# BME280.net
KiCad netlist of a schematic drawn in Altium Designer
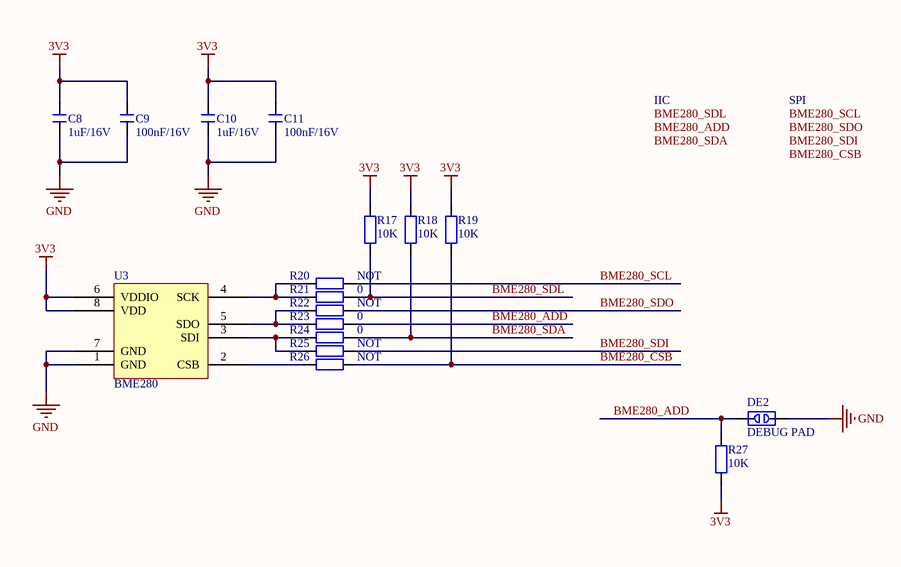
[diagram p0: BME280.SchDoc]

(export (version "E")
  (design (tool "Eeschema 10.0.6"))
  (components
    (comp (ref "C8")
      (value "1uF/16V")
      (footprint "C 0402_L")
      (description "贴片电容")
      (libsource (lib "3.1   - 电阻-电容-电感") (part "C"))
    )
    (comp (ref "C9")
      (value "100nF/16V")
      (footprint "C 0402_L")
      (description "无极性贴片电容")
      (libsource (lib "3.1   - 电阻-电容-电感") (part "C"))
    )
    (comp (ref "C10")
      (value "1uF/16V")
      (footprint "C 0402_L")
      (description "贴片电容")
      (libsource (lib "3.1   - 电阻-电容-电感") (part "C"))
    )
    (comp (ref "C11")
      (value "100nF/16V")
      (footprint "C 0402_L")
      (description "无极性贴片电容")
      (libsource (lib "3.1   - 电阻-电容-电感") (part "C"))
    )
    (comp (ref "DE2")
      (value "DEBUG PAD")
      (footprint "DEBUG_A")
      (description "调试断点焊盘")
      (fields (field (name "版权归属") "源创客"))
      (libsource (lib "15.1 - 未分类器件") (part "DEBUG"))
    )
    (comp (ref "R17")
      (value "10K")
      (footprint "R 0402_L")
      (description "贴片电阻 0402 1%")
      (libsource (lib "3.1   - 电阻-电容-电感") (part "R"))
    )
    (comp (ref "R18")
      (value "10K")
      (footprint "R 0402_L")
      (description "贴片电阻 0402 1%")
      (libsource (lib "3.1   - 电阻-电容-电感") (part "R"))
    )
    (comp (ref "R19")
      (value "10K")
      (footprint "R 0402_L")
      (description "贴片电阻 0402 1%")
      (libsource (lib "3.1   - 电阻-电容-电感") (part "R"))
    )
    (comp (ref "R20")
      (value "NOT")
      (footprint "R 0402_L")
      (description "贴片电阻")
      (libsource (lib "3.1   - 电阻-电容-电感") (part "R"))
    )
    (comp (ref "R21")
      (value "0")
      (footprint "R 0402_L")
      (description "贴片电阻")
      (libsource (lib "3.1   - 电阻-电容-电感") (part "R"))
    )
    (comp (ref "R22")
      (value "NOT")
      (footprint "R 0402_L")
      (description "贴片电阻")
      (libsource (lib "3.1   - 电阻-电容-电感") (part "R"))
    )
    (comp (ref "R23")
      (value "0")
      (footprint "R 0402_L")
      (description "贴片电阻")
      (libsource (lib "3.1   - 电阻-电容-电感") (part "R"))
    )
    (comp (ref "R24")
      (value "0")
      (footprint "R 0402_L")
      (description "贴片电阻")
      (libsource (lib "3.1   - 电阻-电容-电感") (part "R"))
    )
    (comp (ref "R25")
      (value "NOT")
      (footprint "R 0402_L")
      (description "贴片电阻")
      (libsource (lib "3.1   - 电阻-电容-电感") (part "R"))
    )
    (comp (ref "R26")
      (value "NOT")
      (footprint "R 0402_L")
      (description "贴片电阻")
      (libsource (lib "3.1   - 电阻-电容-电感") (part "R"))
    )
    (comp (ref "R27")
      (value "10K")
      (footprint "R 0402_L")
      (description "贴片电阻 0402 1%")
      (libsource (lib "3.1   - 电阻-电容-电感") (part "R"))
    )
    (comp (ref "U3") (value "BME280") (footprint "BME280") (libsource (lib "Schlib1") (part "BME280")))
  )
  (nets
    (net (code "1") (name "/BME280_ADD") (class "Default")
      (node (ref "DE2") (pin "1") (pinfunction "1_1") (pintype "passive"))
      (node (ref "R23") (pin "1") (pinfunction "1_1") (pintype "passive"))
      (node (ref "R27") (pin "2") (pinfunction "2_2") (pintype "passive"))
    )
    (net (code "2") (name "/BME280_CSB") (class "Default")
      (node (ref "R19") (pin "2") (pinfunction "2_2") (pintype "passive"))
      (node (ref "R26") (pin "1") (pinfunction "1_1") (pintype "passive"))
    )
    (net (code "3") (name "/BME280_SCL") (class "Default")
      (node (ref "R20") (pin "1") (pinfunction "1_1") (pintype "passive"))
    )
    (net (code "4") (name "/BME280_SDA") (class "Default")
      (node (ref "R18") (pin "2") (pinfunction "2_2") (pintype "passive"))
      (node (ref "R24") (pin "1") (pinfunction "1_1") (pintype "passive"))
    )
    (net (code "5") (name "/BME280_SDI") (class "Default")
      (node (ref "R25") (pin "1") (pinfunction "1_1") (pintype "passive"))
    )
    (net (code "6") (name "/BME280_SDL") (class "Default")
      (node (ref "R17") (pin "2") (pinfunction "2_2") (pintype "passive"))
      (node (ref "R21") (pin "1") (pinfunction "1_1") (pintype "passive"))
    )
    (net (code "7") (name "/BME280_SDO") (class "Default")
      (node (ref "R22") (pin "1") (pinfunction "1_1") (pintype "passive"))
    )
    (net (code "8") (name "3V3") (class "Default")
      (node (ref "C10") (pin "2") (pinfunction "2_2") (pintype "passive"))
      (node (ref "C11") (pin "1") (pinfunction "1_1") (pintype "passive"))
      (node (ref "C8") (pin "2") (pinfunction "2_2") (pintype "passive"))
      (node (ref "C9") (pin "1") (pinfunction "1_1") (pintype "passive"))
      (node (ref "R17") (pin "1") (pinfunction "1_1") (pintype "passive"))
      (node (ref "R18") (pin "1") (pinfunction "1_1") (pintype "passive"))
      (node (ref "R19") (pin "1") (pinfunction "1_1") (pintype "passive"))
      (node (ref "R27") (pin "1") (pinfunction "1_1") (pintype "passive"))
      (node (ref "U3") (pin "6") (pinfunction "VDDIO_6") (pintype "passive"))
      (node (ref "U3") (pin "8") (pinfunction "VDD_8") (pintype "passive"))
    )
    (net (code "9") (name "GND") (class "Default")
      (node (ref "C10") (pin "1") (pinfunction "1_1") (pintype "passive"))
      (node (ref "C11") (pin "2") (pinfunction "2_2") (pintype "passive"))
      (node (ref "C8") (pin "1") (pinfunction "1_1") (pintype "passive"))
      (node (ref "C9") (pin "2") (pinfunction "2_2") (pintype "passive"))
      (node (ref "DE2") (pin "2") (pinfunction "2_2") (pintype "passive"))
      (node (ref "U3") (pin "1") (pinfunction "GND_1") (pintype "passive"))
      (node (ref "U3") (pin "7") (pinfunction "GND_7") (pintype "passive"))
    )
    (net (code "10") (name "Net-(U3-CSB)") (class "Default")
      (node (ref "R26") (pin "2") (pinfunction "2_2") (pintype "passive"))
      (node (ref "U3") (pin "2") (pinfunction "CSB_2") (pintype "passive"))
    )
    (net (code "11") (name "Net-(U3-SCK)") (class "Default")
      (node (ref "R20") (pin "2") (pinfunction "2_2") (pintype "passive"))
      (node (ref "R21") (pin "2") (pinfunction "2_2") (pintype "passive"))
      (node (ref "U3") (pin "4") (pinfunction "SCK_4") (pintype "passive"))
    )
    (net (code "12") (name "Net-(U3-SDI)") (class "Default")
      (node (ref "R24") (pin "2") (pinfunction "2_2") (pintype "passive"))
      (node (ref "R25") (pin "2") (pinfunction "2_2") (pintype "passive"))
      (node (ref "U3") (pin "3") (pinfunction "SDI_3") (pintype "passive"))
    )
    (net (code "13") (name "Net-(U3-SDO)") (class "Default")
      (node (ref "R22") (pin "2") (pinfunction "2_2") (pintype "passive"))
      (node (ref "R23") (pin "2") (pinfunction "2_2") (pintype "passive"))
      (node (ref "U3") (pin "5") (pinfunction "SDO_5") (pintype "passive"))
    )
  )
)
